# TAC.net
KiCad netlist of a schematic drawn in Altium Designer
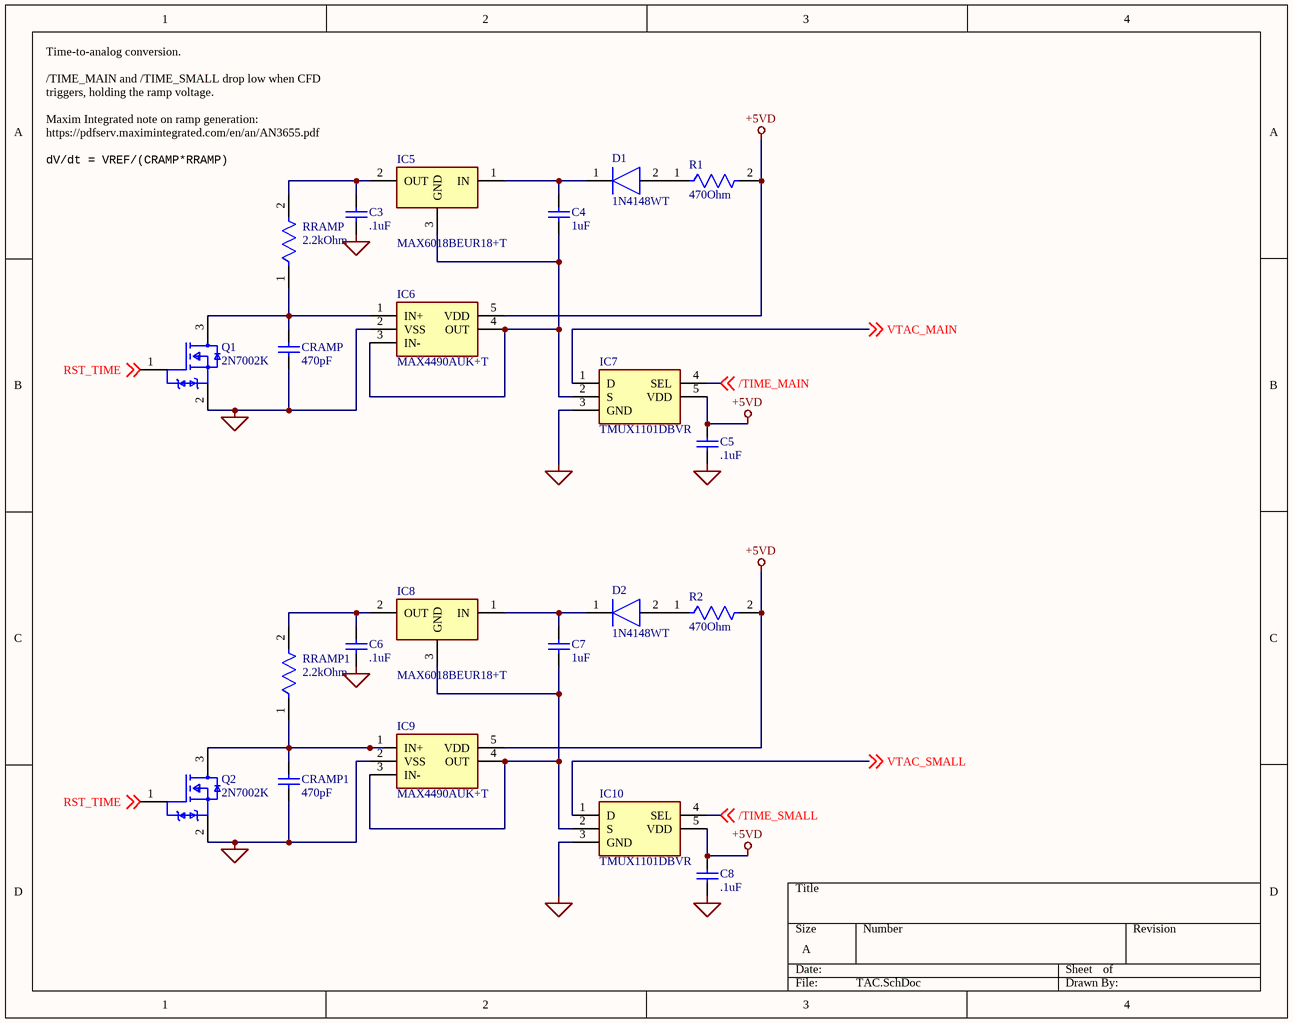
[diagram p0: TAC.SchDoc]

(export (version "E")
  (design (tool "Eeschema 10.0.6"))
  (components
    (comp (ref "C3")
      (value ".1uF")
      (footprint "CAPC2013X140X45NL15T25")
      (description "0402")
      (fields (field (name "PART NUMBER") "GRM21BR71A106KE51L") (field (name "MANUFACTURER") "Murata"))
      (libsource (lib "Altium Content Vault") (part "CAP"))
    )
    (comp (ref "C4")
      (value "1uF")
      (footprint "CAPC2013X140X45NL15T25")
      (description "0402")
      (fields (field (name "PART NUMBER") "GRM21BR71A106KE51L") (field (name "MANUFACTURER") "Murata"))
      (libsource (lib "Altium Content Vault") (part "CAP"))
    )
    (comp (ref "C5")
      (value ".1uF")
      (footprint "CAPC2013X140X45NL15T25")
      (description "0402")
      (fields (field (name "PART NUMBER") "GRM21BR71A106KE51L") (field (name "MANUFACTURER") "Murata"))
      (libsource (lib "Altium Content Vault") (part "CAP"))
    )
    (comp (ref "C6")
      (value ".1uF")
      (footprint "CAPC2013X140X45NL15T25")
      (description "0402")
      (fields (field (name "PART NUMBER") "GRM21BR71A106KE51L") (field (name "MANUFACTURER") "Murata"))
      (libsource (lib "Altium Content Vault") (part "CAP"))
    )
    (comp (ref "C7")
      (value "1uF")
      (footprint "CAPC2013X140X45NL15T25")
      (description "0402")
      (fields (field (name "PART NUMBER") "GRM21BR71A106KE51L") (field (name "MANUFACTURER") "Murata"))
      (libsource (lib "Altium Content Vault") (part "CAP"))
    )
    (comp (ref "C8")
      (value ".1uF")
      (footprint "CAPC2013X140X45NL15T25")
      (description "0402")
      (fields (field (name "PART NUMBER") "GRM21BR71A106KE51L") (field (name "MANUFACTURER") "Murata"))
      (libsource (lib "Altium Content Vault") (part "CAP"))
    )
    (comp (ref "CRAMP")
      (value "470pF")
      (footprint "CAPC2013X140X45NL15T25")
      (description "0402")
      (fields (field (name "PART NUMBER") "GRM21BR71A106KE51L") (field (name "MANUFACTURER") "Murata"))
      (libsource (lib "Altium Content Vault") (part "CAP"))
    )
    (comp (ref "CRAMP1")
      (value "470pF")
      (footprint "CAPC2013X140X45NL15T25")
      (description "0402")
      (fields (field (name "PART NUMBER") "GRM21BR71A106KE51L") (field (name "MANUFACTURER") "Murata"))
      (libsource (lib "Altium Content Vault") (part "CAP"))
    )
    (comp (ref "D1")
      (value "1N4148WT")
      (footprint "SamacSys:SODFL1608X70N")
      (description "Diode")
      (libsource (lib "*") (part "1N4148WT"))
    )
    (comp (ref "D2")
      (value "1N4148WT")
      (footprint "SamacSys:SODFL1608X70N")
      (description "Diode")
      (libsource (lib "*") (part "1N4148WT"))
    )
    (comp (ref "IC5")
      (value "MAX6018BEUR18+T")
      (footprint "SamacSys:SOT95P237X112-3N")
      (description "Voltage References Precision, Micropower, 1.8V Supply, Low-Dropout, SOT23 Voltage Reference")
      (libsource (lib "SamacSys") (part "MAX6018BEUR18+T"))
    )
    (comp (ref "IC6")
      (value "MAX4490AUK+T")
      (footprint "SamacSys:SOT95P280X145-5N")
      (description "Integrated Circuit")
      (libsource (lib "SamacSys") (part "MAX4490AUK+T"))
    )
    (comp (ref "IC7")
      (value "TMUX1101DBVR")
      (footprint "SamacSys:SOT95P280X145-5N")
      (libsource (lib "*") (part "TMUX1101DBVR"))
    )
    (comp (ref "IC8")
      (value "MAX6018BEUR18+T")
      (footprint "SamacSys:SOT95P237X112-3N")
      (description "Voltage References Precision, Micropower, 1.8V Supply, Low-Dropout, SOT23 Voltage Reference")
      (libsource (lib "SamacSys") (part "MAX6018BEUR18+T"))
    )
    (comp (ref "IC9")
      (value "MAX4490AUK+T")
      (footprint "SamacSys:SOT95P280X145-5N")
      (description "Integrated Circuit")
      (libsource (lib "SamacSys") (part "MAX4490AUK+T"))
    )
    (comp (ref "IC10")
      (value "TMUX1101DBVR")
      (footprint "SamacSys:SOT95P280X145-5N")
      (libsource (lib "*") (part "TMUX1101DBVR"))
    )
    (comp (ref "Q1")
      (value "2N7002K")
      (footprint "FP-318-08-MFG")
      (description "MOSFET N-CH 60V 300MA SOT23")
      (fields
        (field (name "OCTOPART") "https://octopart.com/2n7002k-on+semiconductor-84408900")
        (field (name "MANUFACTURER") "ON Semiconductor")
      )
      (libsource (lib "Altium Content Vault") (part "40bafa8609a25cdbb0dab398ef4a0d9"))
    )
    (comp (ref "Q2")
      (value "2N7002K")
      (footprint "FP-318-08-MFG")
      (description "MOSFET N-CH 60V 300MA SOT23")
      (fields
        (field (name "OCTOPART") "https://octopart.com/2n7002k-on+semiconductor-84408900")
        (field (name "MANUFACTURER") "ON Semiconductor")
      )
      (libsource (lib "Altium Content Vault") (part "40bafa8609a25cdbb0dab398ef4a0d9"))
    )
    (comp (ref "R1")
      (value "470Ohm")
      (footprint "FP-CRCW0402-e3-IPC_C")
      (description "RES Thick Film, 0Ω, 0.063W, 0402")
      (fields (field (name "TOLERANCE") "5%"))
      (libsource (lib "Altium Content Vault") (part "1029c3af85768c4190bb7ad29bc67b5"))
    )
    (comp (ref "R2")
      (value "470Ohm")
      (footprint "FP-CRCW0402-e3-IPC_C")
      (description "RES Thick Film, 0Ω, 0.063W, 0402")
      (fields (field (name "TOLERANCE") "5%"))
      (libsource (lib "Altium Content Vault") (part "1029c3af85768c4190bb7ad29bc67b5"))
    )
    (comp (ref "RRAMP")
      (value "2.2kOhm")
      (footprint "FP-CRCW0603-e3-MFG")
      (description "RES Thick Film, 1MΩ, 1%, 0.1W, 100ppm/°C, 0603")
      (fields (field (name "TOLERANCE") "1%"))
      (libsource (lib "Altium Content Vault") (part "1029c3af85768c4190bb7ad29bc67b5"))
    )
    (comp (ref "RRAMP1")
      (value "2.2kOhm")
      (footprint "FP-CRCW0603-e3-MFG")
      (description "RES Thick Film, 1MΩ, 1%, 0.1W, 100ppm/°C, 0603")
      (fields (field (name "TOLERANCE") "1%"))
      (libsource (lib "Altium Content Vault") (part "1029c3af85768c4190bb7ad29bc67b5"))
    )
  )
  (nets
    (net (code "1") (name "+5VD") (class "Default")
      (node (ref "C5") (pin "2") (pinfunction "2_2") (pintype "passive"))
      (node (ref "C8") (pin "2") (pinfunction "2_2") (pintype "passive"))
      (node (ref "IC10") (pin "5") (pinfunction "VDD_5") (pintype "passive"))
      (node (ref "IC6") (pin "5") (pinfunction "VDD_5") (pintype "passive"))
      (node (ref "IC7") (pin "5") (pinfunction "VDD_5") (pintype "passive"))
      (node (ref "IC9") (pin "5") (pinfunction "VDD_5") (pintype "passive"))
      (node (ref "R1") (pin "2") (pinfunction "2_2") (pintype "passive"))
      (node (ref "R2") (pin "2") (pinfunction "2_2") (pintype "passive"))
    )
    (net (code "2") (name "GND") (class "Default")
      (node (ref "C3") (pin "1") (pinfunction "1_1") (pintype "passive"))
      (node (ref "C5") (pin "1") (pinfunction "1_1") (pintype "passive"))
      (node (ref "C6") (pin "1") (pinfunction "1_1") (pintype "passive"))
      (node (ref "C8") (pin "1") (pinfunction "1_1") (pintype "passive"))
      (node (ref "CRAMP") (pin "1") (pinfunction "1_1") (pintype "passive"))
      (node (ref "CRAMP1") (pin "1") (pinfunction "1_1") (pintype "passive"))
      (node (ref "IC10") (pin "3") (pinfunction "GND_3") (pintype "passive"))
      (node (ref "IC6") (pin "2") (pinfunction "VSS_2") (pintype "passive"))
      (node (ref "IC7") (pin "3") (pinfunction "GND_3") (pintype "passive"))
      (node (ref "IC9") (pin "2") (pinfunction "VSS_2") (pintype "passive"))
      (node (ref "Q1") (pin "2") (pinfunction "Source_2") (pintype "passive"))
      (node (ref "Q2") (pin "2") (pinfunction "Source_2") (pintype "passive"))
    )
    (net (code "3") (name "Net-(D1-A)") (class "Default")
      (node (ref "D1") (pin "2") (pinfunction "A_2") (pintype "passive"))
      (node (ref "R1") (pin "1") (pinfunction "1_1") (pintype "passive"))
    )
    (net (code "4") (name "Net-(D1-K)") (class "Default")
      (node (ref "C4") (pin "2") (pinfunction "2_2") (pintype "passive"))
      (node (ref "D1") (pin "1") (pinfunction "K_1") (pintype "passive"))
      (node (ref "IC5") (pin "1") (pinfunction "IN_1") (pintype "passive"))
    )
    (net (code "5") (name "Net-(D2-A)") (class "Default")
      (node (ref "D2") (pin "2") (pinfunction "A_2") (pintype "passive"))
      (node (ref "R2") (pin "1") (pinfunction "1_1") (pintype "passive"))
    )
    (net (code "6") (name "Net-(D2-K)") (class "Default")
      (node (ref "C7") (pin "2") (pinfunction "2_2") (pintype "passive"))
      (node (ref "D2") (pin "1") (pinfunction "K_1") (pintype "passive"))
      (node (ref "IC8") (pin "1") (pinfunction "IN_1") (pintype "passive"))
    )
    (net (code "7") (name "Net-(IC5-GND)") (class "Default")
      (node (ref "C4") (pin "1") (pinfunction "1_1") (pintype "passive"))
      (node (ref "IC5") (pin "3") (pinfunction "GND_3") (pintype "passive"))
      (node (ref "IC6") (pin "3") (pinfunction "IN-_3") (pintype "passive"))
      (node (ref "IC6") (pin "4") (pinfunction "OUT_4") (pintype "passive"))
      (node (ref "IC7") (pin "2") (pinfunction "S_2") (pintype "passive"))
    )
    (net (code "8") (name "Net-(IC5-OUT)") (class "Default")
      (node (ref "C3") (pin "2") (pinfunction "2_2") (pintype "passive"))
      (node (ref "IC5") (pin "2") (pinfunction "OUT_2") (pintype "passive"))
      (node (ref "RRAMP") (pin "2") (pinfunction "2_2") (pintype "passive"))
    )
    (net (code "9") (name "Net-(IC6-IN+)") (class "Default")
      (node (ref "CRAMP") (pin "2") (pinfunction "2_2") (pintype "passive"))
      (node (ref "IC6") (pin "1") (pinfunction "IN+_1") (pintype "passive"))
      (node (ref "Q1") (pin "3") (pinfunction "Drain_3") (pintype "passive"))
      (node (ref "RRAMP") (pin "1") (pinfunction "1_1") (pintype "passive"))
    )
    (net (code "10") (name "Net-(IC8-OUT)") (class "Default")
      (node (ref "C6") (pin "2") (pinfunction "2_2") (pintype "passive"))
      (node (ref "IC8") (pin "2") (pinfunction "OUT_2") (pintype "passive"))
      (node (ref "RRAMP1") (pin "2") (pinfunction "2_2") (pintype "passive"))
    )
    (net (code "11") (name "Net-(IC9-IN+)") (class "Default")
      (node (ref "CRAMP1") (pin "2") (pinfunction "2_2") (pintype "passive"))
      (node (ref "IC9") (pin "1") (pinfunction "IN+_1") (pintype "passive"))
      (node (ref "Q2") (pin "3") (pinfunction "Drain_3") (pintype "passive"))
      (node (ref "RRAMP1") (pin "1") (pinfunction "1_1") (pintype "passive"))
    )
    (net (code "12") (name "Net-(IC10-S)") (class "Default")
      (node (ref "C7") (pin "1") (pinfunction "1_1") (pintype "passive"))
      (node (ref "IC10") (pin "2") (pinfunction "S_2") (pintype "passive"))
      (node (ref "IC8") (pin "3") (pinfunction "GND_3") (pintype "passive"))
      (node (ref "IC9") (pin "3") (pinfunction "IN-_3") (pintype "passive"))
      (node (ref "IC9") (pin "4") (pinfunction "OUT_4") (pintype "passive"))
    )
    (net (code "13") (name "RST_TIME") (class "Default")
      (node (ref "Q1") (pin "1") (pinfunction "Gate_1") (pintype "passive"))
      (node (ref "Q2") (pin "1") (pinfunction "Gate_1") (pintype "passive"))
    )
    (net (code "14") (name "VTAC_MAIN") (class "Default")
      (node (ref "IC7") (pin "1") (pinfunction "D_1") (pintype "passive"))
    )
    (net (code "15") (name "VTAC_SMALL") (class "Default")
      (node (ref "IC10") (pin "1") (pinfunction "D_1") (pintype "passive"))
    )
    (net (code "16") (name "{slash}TIME_MAIN") (class "Default")
      (node (ref "IC7") (pin "4") (pinfunction "SEL_4") (pintype "passive"))
    )
    (net (code "17") (name "{slash}TIME_SMALL") (class "Default")
      (node (ref "IC10") (pin "4") (pinfunction "SEL_4") (pintype "passive"))
    )
  )
)
